# Esquem_tico_e_Layout_-_BitControl.net
KiCad netlist of a schematic drawn in EasyEDA Pro
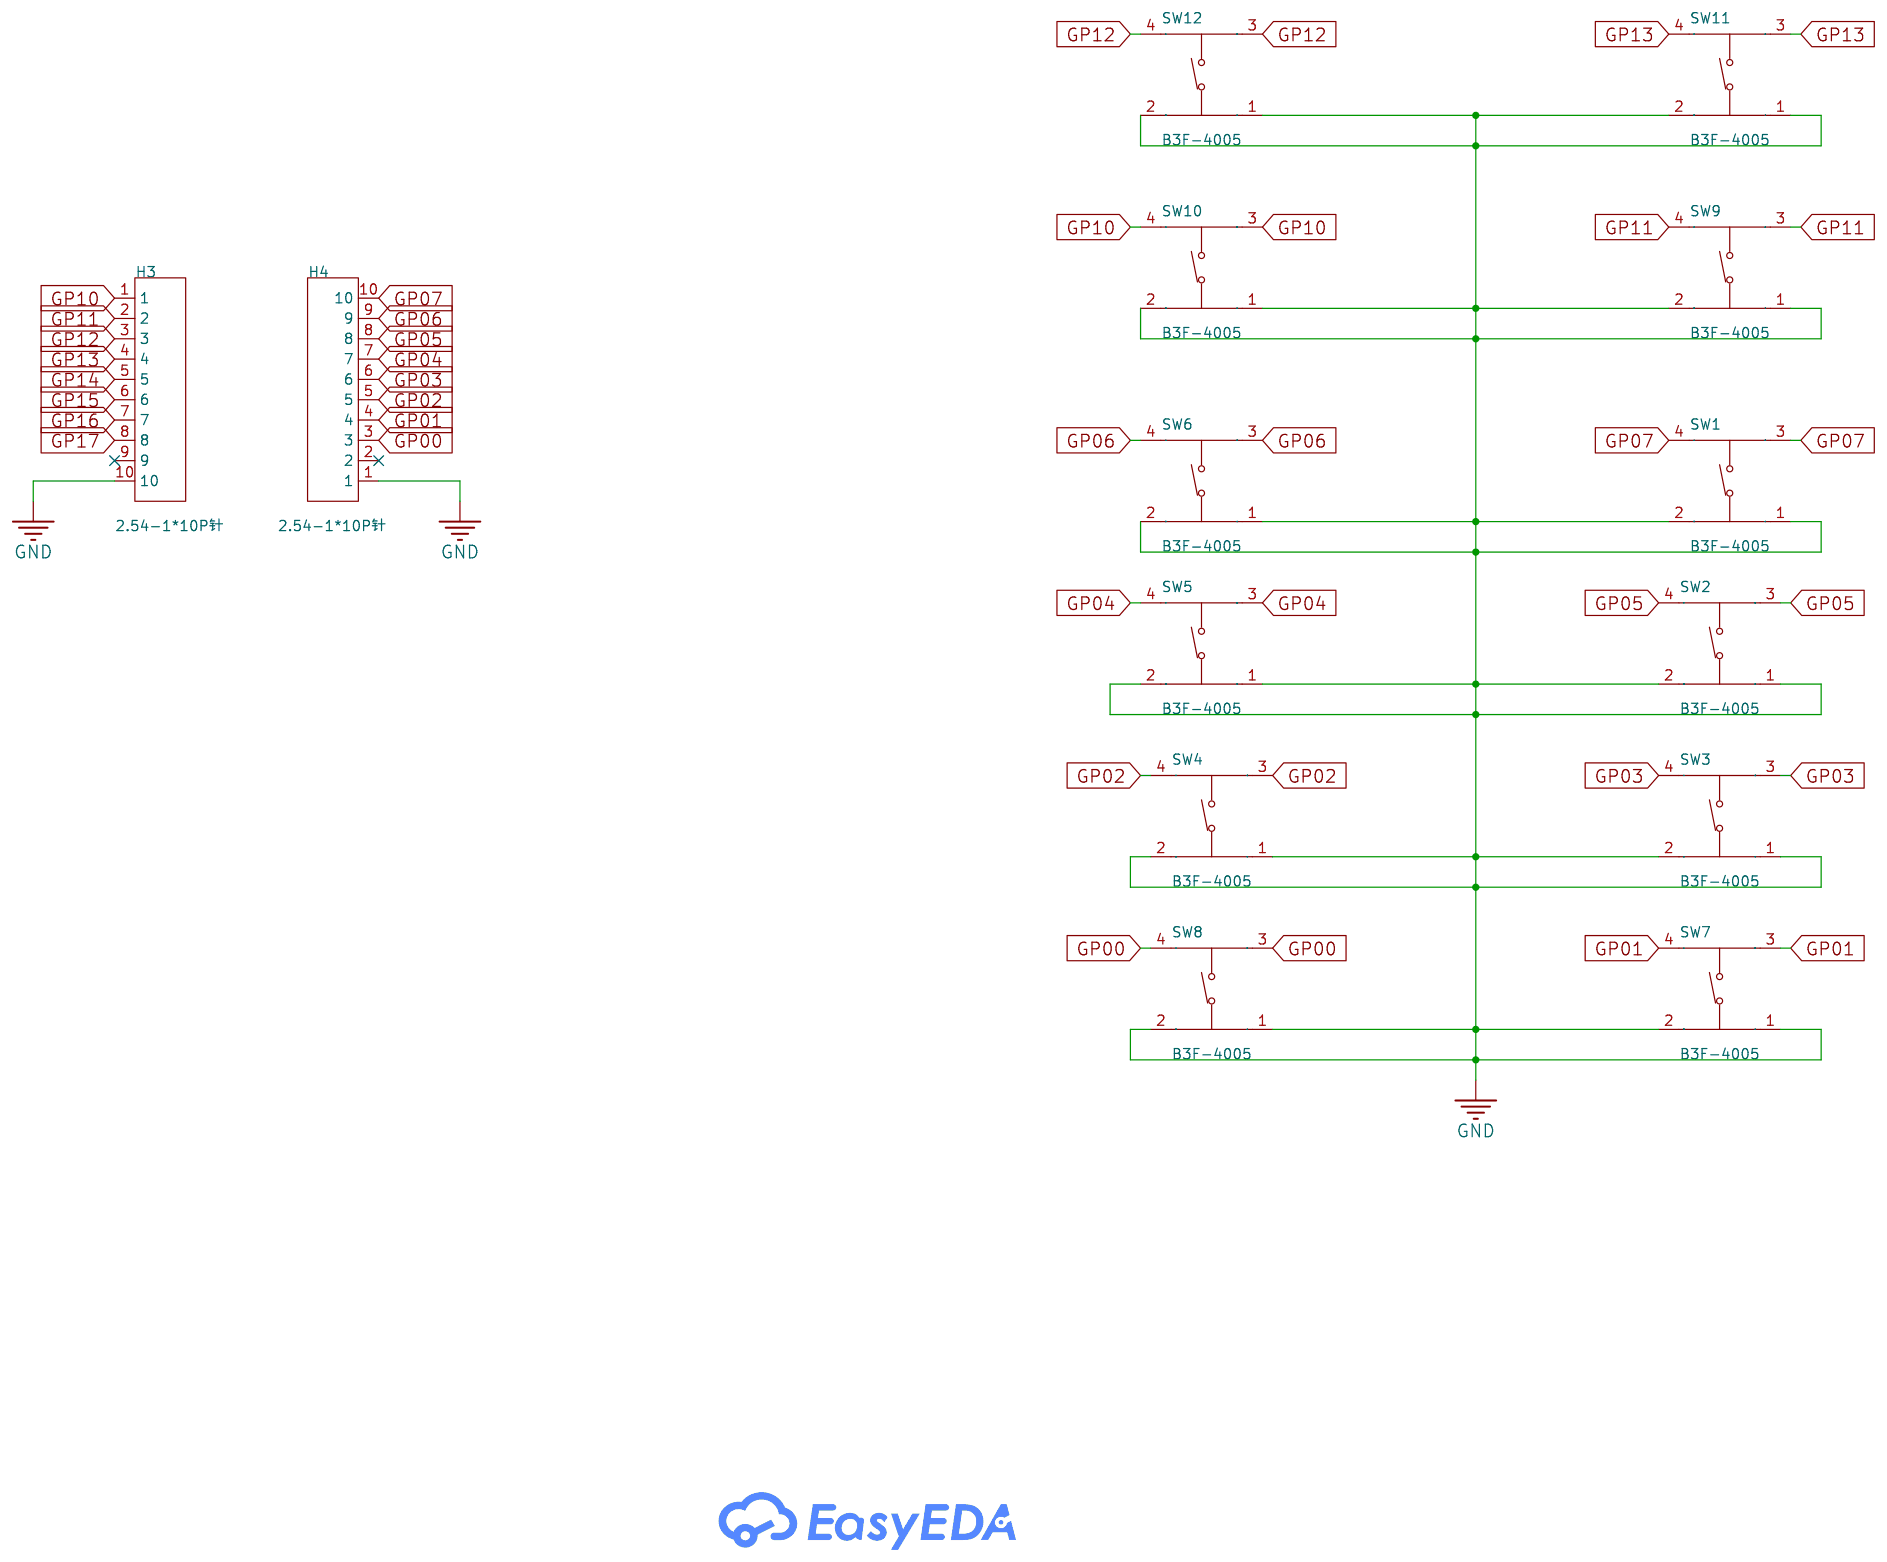
[diagram p0: schematic sheet]

(export (version "E")
  (design (tool "Eeschema 10.0.6"))
  (components
    (comp (ref "H3")
      (value "2.54-1*10P针")
      (footprint "easyedapro:HDR-TH_10P-P2.54-V-M-1")
      (fields (field (name "Manufacturer") "BOOMELE(博穆精密)"))
      (libsource (lib "easyedapro") (part "Header-Male-2.54_1x10"))
    )
    (comp (ref "H4")
      (value "2.54-1*10P针")
      (footprint "easyedapro:HDR-TH_10P-P2.54-V-M-1")
      (fields (field (name "Manufacturer") "BOOMELE(博穆精密)"))
      (libsource (lib "easyedapro") (part "Header-Male-2.54_1x10"))
    )
    (comp (ref "SW1")
      (value "B3F-4005")
      (footprint "easyedapro:SW-TH_4P-L12.0-W12.0-P5.00-LS12.5-EH")
      (fields (field (name "Manufacturer") "OMRON(欧姆龙)"))
      (libsource (lib "easyedapro") (part "B3F-4005_C397283"))
    )
    (comp (ref "SW2")
      (value "B3F-4005")
      (footprint "easyedapro:SW-TH_4P-L12.0-W12.0-P5.00-LS12.5-EH")
      (fields (field (name "Manufacturer") "OMRON(欧姆龙)"))
      (libsource (lib "easyedapro") (part "B3F-4005_C397283"))
    )
    (comp (ref "SW3")
      (value "B3F-4005")
      (footprint "easyedapro:SW-TH_4P-L12.0-W12.0-P5.00-LS12.5-EH")
      (fields (field (name "Manufacturer") "OMRON(欧姆龙)"))
      (libsource (lib "easyedapro") (part "B3F-4005_C397283"))
    )
    (comp (ref "SW4")
      (value "B3F-4005")
      (footprint "easyedapro:SW-TH_4P-L12.0-W12.0-P5.00-LS12.5-EH")
      (fields (field (name "Manufacturer") "OMRON(欧姆龙)"))
      (libsource (lib "easyedapro") (part "B3F-4005_C397283"))
    )
    (comp (ref "SW5")
      (value "B3F-4005")
      (footprint "easyedapro:SW-TH_4P-L12.0-W12.0-P5.00-LS12.5-EH")
      (fields (field (name "Manufacturer") "OMRON(欧姆龙)"))
      (libsource (lib "easyedapro") (part "B3F-4005_C397283"))
    )
    (comp (ref "SW6")
      (value "B3F-4005")
      (footprint "easyedapro:SW-TH_4P-L12.0-W12.0-P5.00-LS12.5-EH")
      (fields (field (name "Manufacturer") "OMRON(欧姆龙)"))
      (libsource (lib "easyedapro") (part "B3F-4005_C397283"))
    )
    (comp (ref "SW7")
      (value "B3F-4005")
      (footprint "easyedapro:SW-TH_4P-L12.0-W12.0-P5.00-LS12.5-EH")
      (fields (field (name "Manufacturer") "OMRON(欧姆龙)"))
      (libsource (lib "easyedapro") (part "B3F-4005_C397283"))
    )
    (comp (ref "SW8")
      (value "B3F-4005")
      (footprint "easyedapro:SW-TH_4P-L12.0-W12.0-P5.00-LS12.5-EH")
      (fields (field (name "Manufacturer") "OMRON(欧姆龙)"))
      (libsource (lib "easyedapro") (part "B3F-4005_C397283"))
    )
    (comp (ref "SW9")
      (value "B3F-4005")
      (footprint "easyedapro:SW-TH_4P-L12.0-W12.0-P5.00-LS12.5-EH")
      (fields (field (name "Manufacturer") "OMRON(欧姆龙)"))
      (libsource (lib "easyedapro") (part "B3F-4005_C397283"))
    )
    (comp (ref "SW10")
      (value "B3F-4005")
      (footprint "easyedapro:SW-TH_4P-L12.0-W12.0-P5.00-LS12.5-EH")
      (fields (field (name "Manufacturer") "OMRON(欧姆龙)"))
      (libsource (lib "easyedapro") (part "B3F-4005_C397283"))
    )
    (comp (ref "SW11")
      (value "B3F-4005")
      (footprint "easyedapro:SW-TH_4P-L12.0-W12.0-P5.00-LS12.5-EH")
      (fields (field (name "Manufacturer") "OMRON(欧姆龙)"))
      (libsource (lib "easyedapro") (part "B3F-4005_C397283"))
    )
    (comp (ref "SW12")
      (value "B3F-4005")
      (footprint "easyedapro:SW-TH_4P-L12.0-W12.0-P5.00-LS12.5-EH")
      (fields (field (name "Manufacturer") "OMRON(欧姆龙)"))
      (libsource (lib "easyedapro") (part "B3F-4005_C397283"))
    )
  )
  (nets
    (net (code "1") (name "GND") (class "Default")
      (node (ref "H3") (pin "10") (pinfunction "10_10") (pintype "unspecified"))
      (node (ref "H4") (pin "1") (pinfunction "1_1") (pintype "unspecified"))
      (node (ref "SW1") (pin "1") (pinfunction "1_1") (pintype "unspecified"))
      (node (ref "SW1") (pin "2") (pinfunction "2_2") (pintype "unspecified"))
      (node (ref "SW10") (pin "1") (pinfunction "1_1") (pintype "unspecified"))
      (node (ref "SW10") (pin "2") (pinfunction "2_2") (pintype "unspecified"))
      (node (ref "SW11") (pin "1") (pinfunction "1_1") (pintype "unspecified"))
      (node (ref "SW11") (pin "2") (pinfunction "2_2") (pintype "unspecified"))
      (node (ref "SW12") (pin "1") (pinfunction "1_1") (pintype "unspecified"))
      (node (ref "SW12") (pin "2") (pinfunction "2_2") (pintype "unspecified"))
      (node (ref "SW2") (pin "1") (pinfunction "1_1") (pintype "unspecified"))
      (node (ref "SW2") (pin "2") (pinfunction "2_2") (pintype "unspecified"))
      (node (ref "SW3") (pin "1") (pinfunction "1_1") (pintype "unspecified"))
      (node (ref "SW3") (pin "2") (pinfunction "2_2") (pintype "unspecified"))
      (node (ref "SW4") (pin "1") (pinfunction "1_1") (pintype "unspecified"))
      (node (ref "SW4") (pin "2") (pinfunction "2_2") (pintype "unspecified"))
      (node (ref "SW5") (pin "1") (pinfunction "1_1") (pintype "unspecified"))
      (node (ref "SW5") (pin "2") (pinfunction "2_2") (pintype "unspecified"))
      (node (ref "SW6") (pin "1") (pinfunction "1_1") (pintype "unspecified"))
      (node (ref "SW6") (pin "2") (pinfunction "2_2") (pintype "unspecified"))
      (node (ref "SW7") (pin "1") (pinfunction "1_1") (pintype "unspecified"))
      (node (ref "SW7") (pin "2") (pinfunction "2_2") (pintype "unspecified"))
      (node (ref "SW8") (pin "1") (pinfunction "1_1") (pintype "unspecified"))
      (node (ref "SW8") (pin "2") (pinfunction "2_2") (pintype "unspecified"))
      (node (ref "SW9") (pin "1") (pinfunction "1_1") (pintype "unspecified"))
      (node (ref "SW9") (pin "2") (pinfunction "2_2") (pintype "unspecified"))
    )
    (net (code "2") (name "GP00") (class "Default")
      (node (ref "H4") (pin "3") (pinfunction "3_3") (pintype "unspecified"))
      (node (ref "SW8") (pin "3") (pinfunction "3_3") (pintype "unspecified"))
      (node (ref "SW8") (pin "4") (pinfunction "4_4") (pintype "unspecified"))
    )
    (net (code "3") (name "GP01") (class "Default")
      (node (ref "H4") (pin "4") (pinfunction "4_4") (pintype "unspecified"))
      (node (ref "SW7") (pin "3") (pinfunction "3_3") (pintype "unspecified"))
      (node (ref "SW7") (pin "4") (pinfunction "4_4") (pintype "unspecified"))
    )
    (net (code "4") (name "GP02") (class "Default")
      (node (ref "H4") (pin "5") (pinfunction "5_5") (pintype "unspecified"))
      (node (ref "SW4") (pin "3") (pinfunction "3_3") (pintype "unspecified"))
      (node (ref "SW4") (pin "4") (pinfunction "4_4") (pintype "unspecified"))
    )
    (net (code "5") (name "GP03") (class "Default")
      (node (ref "H4") (pin "6") (pinfunction "6_6") (pintype "unspecified"))
      (node (ref "SW3") (pin "3") (pinfunction "3_3") (pintype "unspecified"))
      (node (ref "SW3") (pin "4") (pinfunction "4_4") (pintype "unspecified"))
    )
    (net (code "6") (name "GP04") (class "Default")
      (node (ref "H4") (pin "7") (pinfunction "7_7") (pintype "unspecified"))
      (node (ref "SW5") (pin "3") (pinfunction "3_3") (pintype "unspecified"))
      (node (ref "SW5") (pin "4") (pinfunction "4_4") (pintype "unspecified"))
    )
    (net (code "7") (name "GP05") (class "Default")
      (node (ref "H4") (pin "8") (pinfunction "8_8") (pintype "unspecified"))
      (node (ref "SW2") (pin "3") (pinfunction "3_3") (pintype "unspecified"))
      (node (ref "SW2") (pin "4") (pinfunction "4_4") (pintype "unspecified"))
    )
    (net (code "8") (name "GP06") (class "Default")
      (node (ref "H4") (pin "9") (pinfunction "9_9") (pintype "unspecified"))
      (node (ref "SW6") (pin "3") (pinfunction "3_3") (pintype "unspecified"))
      (node (ref "SW6") (pin "4") (pinfunction "4_4") (pintype "unspecified"))
    )
    (net (code "9") (name "GP07") (class "Default")
      (node (ref "H4") (pin "10") (pinfunction "10_10") (pintype "unspecified"))
      (node (ref "SW1") (pin "3") (pinfunction "3_3") (pintype "unspecified"))
      (node (ref "SW1") (pin "4") (pinfunction "4_4") (pintype "unspecified"))
    )
    (net (code "10") (name "GP10") (class "Default")
      (node (ref "H3") (pin "1") (pinfunction "1_1") (pintype "unspecified"))
      (node (ref "SW10") (pin "3") (pinfunction "3_3") (pintype "unspecified"))
      (node (ref "SW10") (pin "4") (pinfunction "4_4") (pintype "unspecified"))
    )
    (net (code "11") (name "GP11") (class "Default")
      (node (ref "H3") (pin "2") (pinfunction "2_2") (pintype "unspecified"))
      (node (ref "SW9") (pin "3") (pinfunction "3_3") (pintype "unspecified"))
      (node (ref "SW9") (pin "4") (pinfunction "4_4") (pintype "unspecified"))
    )
    (net (code "12") (name "GP12") (class "Default")
      (node (ref "H3") (pin "3") (pinfunction "3_3") (pintype "unspecified"))
      (node (ref "SW12") (pin "3") (pinfunction "3_3") (pintype "unspecified"))
      (node (ref "SW12") (pin "4") (pinfunction "4_4") (pintype "unspecified"))
    )
    (net (code "13") (name "GP13") (class "Default")
      (node (ref "H3") (pin "4") (pinfunction "4_4") (pintype "unspecified"))
      (node (ref "SW11") (pin "3") (pinfunction "3_3") (pintype "unspecified"))
      (node (ref "SW11") (pin "4") (pinfunction "4_4") (pintype "unspecified"))
    )
    (net (code "14") (name "GP14") (class "Default")
      (node (ref "H3") (pin "5") (pinfunction "5_5") (pintype "unspecified"))
    )
    (net (code "15") (name "GP15") (class "Default")
      (node (ref "H3") (pin "6") (pinfunction "6_6") (pintype "unspecified"))
    )
    (net (code "16") (name "GP16") (class "Default")
      (node (ref "H3") (pin "7") (pinfunction "7_7") (pintype "unspecified"))
    )
    (net (code "17") (name "GP17") (class "Default")
      (node (ref "H3") (pin "8") (pinfunction "8_8") (pintype "unspecified"))
    )
    (net (code "18") (name "unconnected-(H3-Pad9)") (class "Default")
      (node (ref "H3") (pin "9") (pinfunction "9_9") (pintype "unspecified+no_connect"))
    )
    (net (code "19") (name "unconnected-(H4-Pad2)") (class "Default")
      (node (ref "H4") (pin "2") (pinfunction "2_2") (pintype "unspecified+no_connect"))
    )
  )
)
